# neojoint-splitter.net
KiCad netlist of a schematic drawn in EAGLE
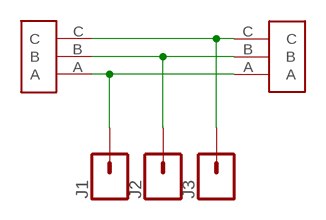
[diagram p0: schematic, sheet 1]

(export (version "E")
  (design (tool "Eeschema 10.0.6"))
  (components
    (comp (ref "J1")
      (value "CONN_01")
      (footprint "eagle-import:1X01")
      (libsource (lib "eagle-import") (part "CONN_01"))
    )
    (comp (ref "J2")
      (value "CONN_01")
      (footprint "eagle-import:1X01")
      (libsource (lib "eagle-import") (part "CONN_01"))
    )
    (comp (ref "J3")
      (value "CONN_01")
      (footprint "eagle-import:1X01")
      (libsource (lib "eagle-import") (part "CONN_01"))
    )
    (comp (ref "U$1")
      (value "LED_STRIP_3P")
      (footprint "eagle-import:LEDSTRIP-3P")
      (libsource (lib "eagle-import") (part "LED_STRIP_3P"))
    )
    (comp (ref "U$2")
      (value "LED_STRIP_3P")
      (footprint "eagle-import:LEDSTRIP-3P")
      (libsource (lib "eagle-import") (part "LED_STRIP_3P"))
    )
  )
  (nets
    (net (code "1") (name "Net-(J1-Pad1)") (class "Default")
      (node (ref "J1") (pin "1") (pinfunction "1_1") (pintype "passive"))
      (node (ref "U$1") (pin "A") (pinfunction "A_A") (pintype "bidirectional"))
      (node (ref "U$2") (pin "A") (pinfunction "A_A") (pintype "bidirectional"))
    )
    (net (code "2") (name "Net-(J2-Pad1)") (class "Default")
      (node (ref "J2") (pin "1") (pinfunction "1_1") (pintype "passive"))
      (node (ref "U$1") (pin "B") (pinfunction "B_B") (pintype "bidirectional"))
      (node (ref "U$2") (pin "B") (pinfunction "B_B") (pintype "bidirectional"))
    )
    (net (code "3") (name "Net-(J3-Pad1)") (class "Default")
      (node (ref "J3") (pin "1") (pinfunction "1_1") (pintype "passive"))
      (node (ref "U$1") (pin "C") (pinfunction "C_C") (pintype "bidirectional"))
      (node (ref "U$2") (pin "C") (pinfunction "C_C") (pintype "bidirectional"))
    )
  )
)
